# DebuggerConnectors.net
KiCad netlist of a schematic drawn in Altium Designer
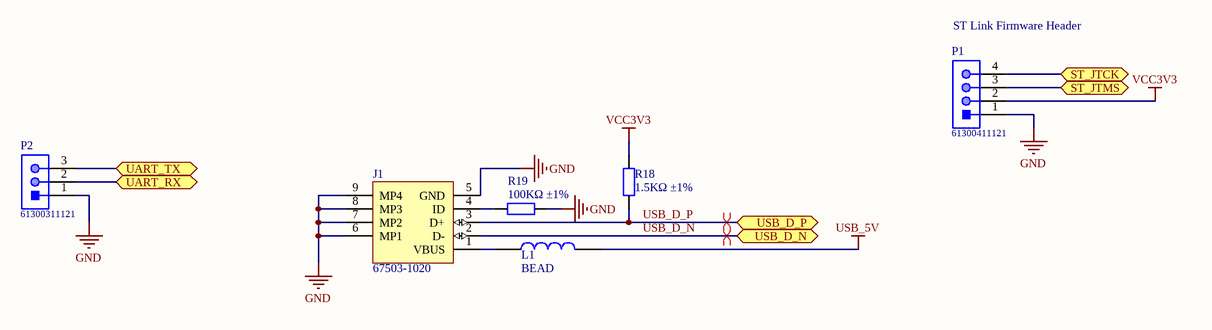
[diagram p0: DebuggerConnectors.SchDoc]

(export (version "E")
  (design (tool "Eeschema 10.0.6"))
  (components
    (comp (ref "J1")
      (value "67503-1020")
      (footprint "MOLX-67503-1020_V")
      (description "USB, MINI, SMD, RA KME04-USBMU03A01")
      (fields (field (name "MANUFACTURER") "Molex"))
      (libsource (lib "Altium Content Vault") (part "MOLX-67503-1020"))
    )
    (comp (ref "L1")
      (value "BEAD")
      (footprint "0603_L")
      (description "Ferrite Bead")
      (libsource (lib "FBEAD") (part "0603 100R@100Mhz 1A"))
    )
    (comp (ref "P1")
      (value "61300411121")
      (footprint "61300411121")
      (description "THT Vertical Pin Header WR-PHD, Pitch 2.54 mm, Single Row, 4 pins")
      (fields (field (name "MANUFACTURER") "Wurth Elektronik") (field (name "PUBLISHER") "WurthElektronik"))
      (libsource (lib "Altium Content Vault") (part "WE-CN-1P-M-R4"))
    )
    (comp (ref "P2")
      (value "61300311121")
      (footprint "61300311121")
      (description "THT Vertical Pin Header WR-PHD, Pitch 2.54 mm, Single Row, 3 pins")
      (fields (field (name "MANUFACTURER") "Wurth Elektronik") (field (name "PUBLISHER") "WurthElektronik"))
      (libsource (lib "Altium Content Vault") (part "WE-CN-1P-M-R3"))
    )
    (comp (ref "R18")
      (value "1.5KΩ ±1%")
      (footprint "0402_R")
      (description "Chip resistor")
      (fields (field (name "MANUFACTURER") "Uniroyal Elec") (field (name "PARTNUMBER") "0402WGF1501TCE"))
      (libsource (lib "Miscellaneous Devices LC") (part "0402 1.5K (1501) 1%"))
    )
    (comp (ref "R19")
      (value "100KΩ ±1%")
      (footprint "0402_R")
      (description "Chip resistor")
      (fields (field (name "MANUFACTURER") "Uniroyal Elec") (field (name "PARTNUMBER") "0402WGF1003TCE"))
      (libsource (lib "Miscellaneous Devices LC") (part "0402 100K (1003) 1%"))
    )
  )
  (nets
    (net (code "1") (name "/ST_JTCK") (class "Default")
      (node (ref "P1") (pin "4") (pinfunction "4_4") (pintype "passive"))
    )
    (net (code "2") (name "/ST_JTMS") (class "Default")
      (node (ref "P1") (pin "3") (pinfunction "3_3") (pintype "passive"))
    )
    (net (code "3") (name "/UART_RX") (class "Default")
      (node (ref "P2") (pin "2") (pinfunction "2_2") (pintype "passive"))
    )
    (net (code "4") (name "/UART_TX") (class "Default")
      (node (ref "P2") (pin "3") (pinfunction "3_3") (pintype "passive"))
    )
    (net (code "5") (name "/USB_D_N") (class "Default")
      (node (ref "J1") (pin "2") (pinfunction "D-_2") (pintype "bidirectional"))
    )
    (net (code "6") (name "/USB_D_P") (class "Default")
      (node (ref "J1") (pin "3") (pinfunction "D+_3") (pintype "bidirectional"))
      (node (ref "R18") (pin "1") (pinfunction "1_1") (pintype "passive"))
    )
    (net (code "7") (name "GND") (class "Default")
      (node (ref "J1") (pin "5") (pinfunction "GND_5") (pintype "power_in"))
      (node (ref "J1") (pin "6") (pinfunction "MP1_6") (pintype "passive"))
      (node (ref "J1") (pin "7") (pinfunction "MP2_7") (pintype "passive"))
      (node (ref "J1") (pin "8") (pinfunction "MP3_8") (pintype "passive"))
      (node (ref "J1") (pin "9") (pinfunction "MP4_9") (pintype "passive"))
      (node (ref "P1") (pin "1") (pinfunction "1_1") (pintype "passive"))
      (node (ref "P2") (pin "1") (pinfunction "1_1") (pintype "passive"))
      (node (ref "R19") (pin "2") (pinfunction "2_2") (pintype "passive"))
    )
    (net (code "8") (name "Net-(J1-ID)") (class "Default")
      (node (ref "J1") (pin "4") (pinfunction "ID_4") (pintype "passive"))
      (node (ref "R19") (pin "1") (pinfunction "1_1") (pintype "passive"))
    )
    (net (code "9") (name "Net-(J1-VBUS)") (class "Default")
      (node (ref "J1") (pin "1") (pinfunction "VBUS_1") (pintype "power_in"))
      (node (ref "L1") (pin "1") (pinfunction "1_1") (pintype "passive"))
    )
    (net (code "10") (name "USB_5V") (class "Default")
      (node (ref "L1") (pin "2") (pinfunction "2_2") (pintype "passive"))
    )
    (net (code "11") (name "VCC3V3") (class "Default")
      (node (ref "P1") (pin "2") (pinfunction "2_2") (pintype "passive"))
      (node (ref "R18") (pin "2") (pinfunction "2_2") (pintype "passive"))
    )
  )
)
